# 19_RK3588_1_8V__3_3V_GPIO.net
KiCad netlist of a schematic drawn in Altium Designer
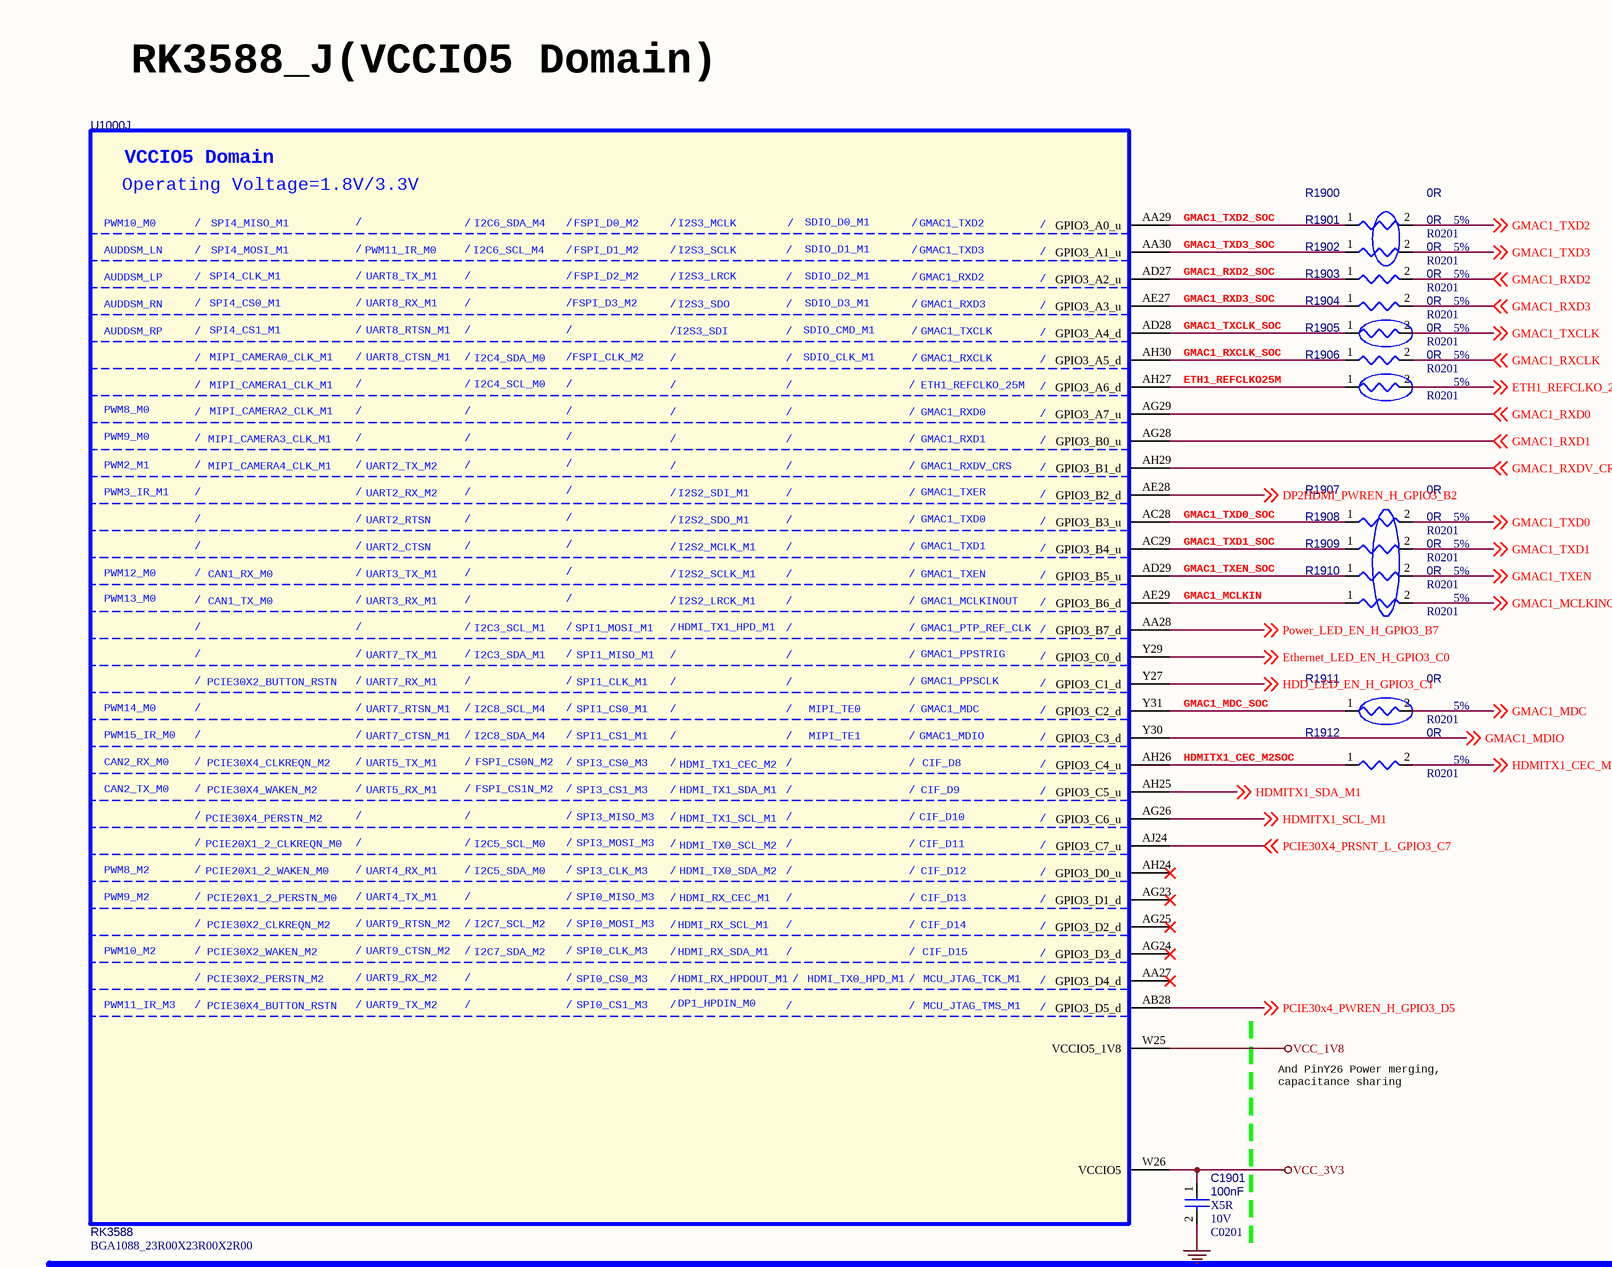
[diagram p0: 19.RK3588_1.8V_ 3.3V GPIO.SchDoc, top left]
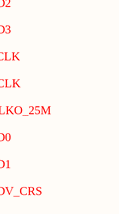
[diagram p1: 19.RK3588_1.8V_ 3.3V GPIO.SchDoc, top right]
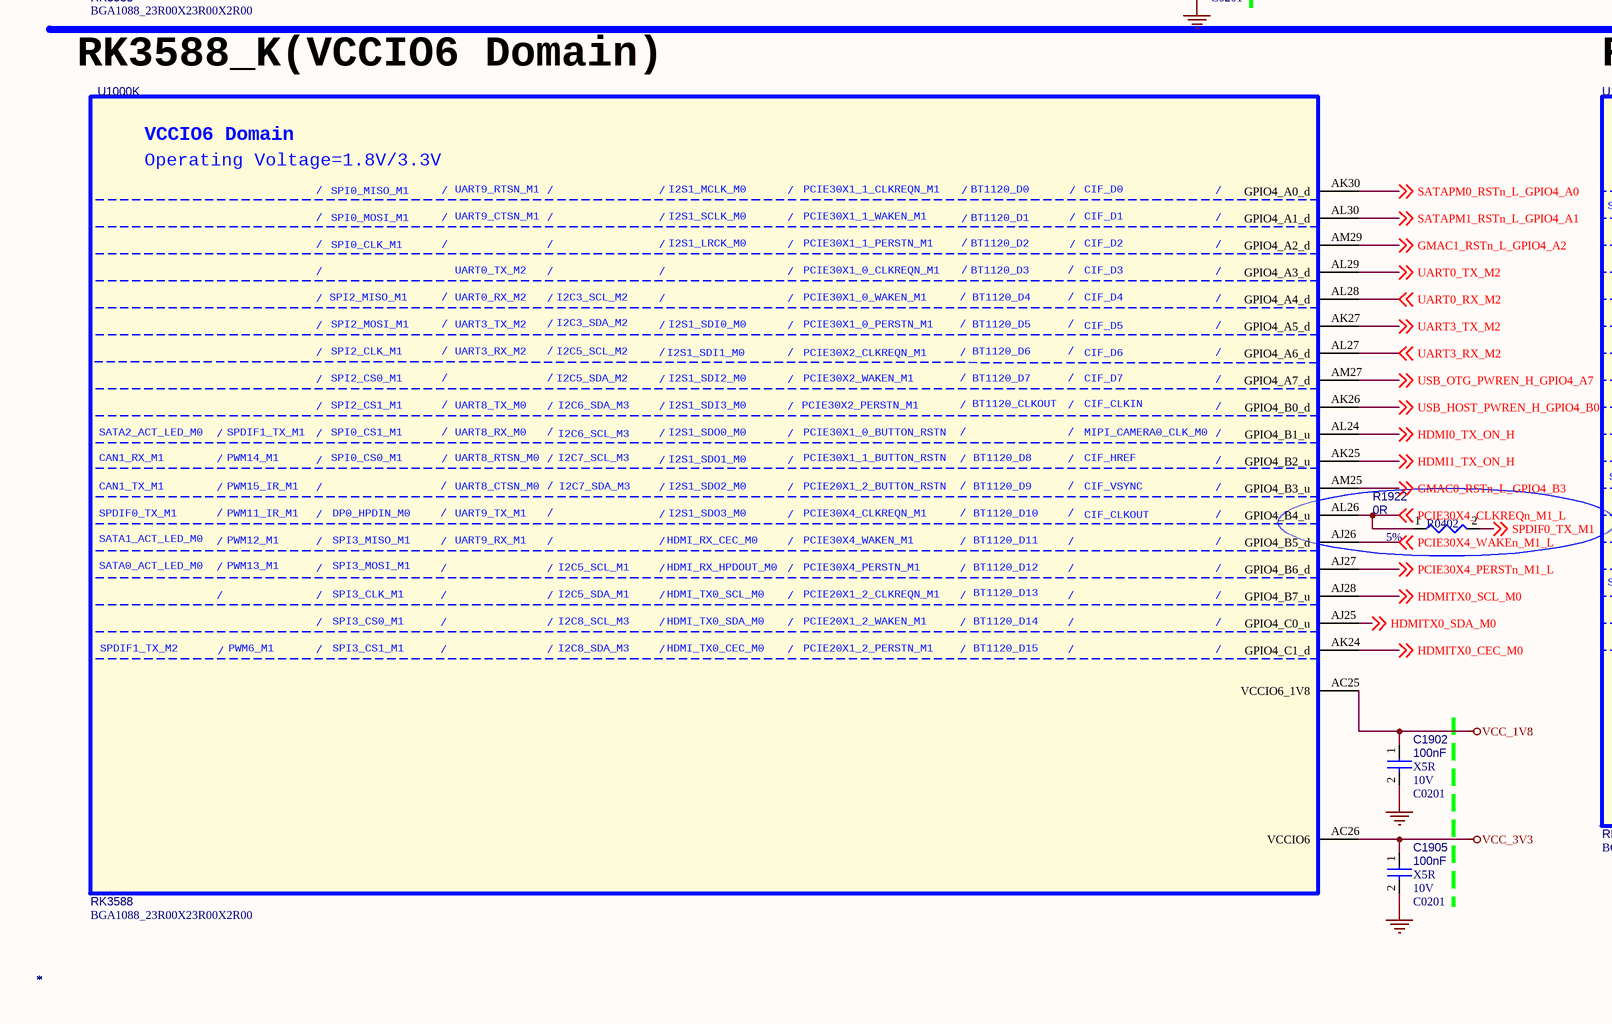
[diagram p2: 19.RK3588_1.8V_ 3.3V GPIO.SchDoc, bottom left]
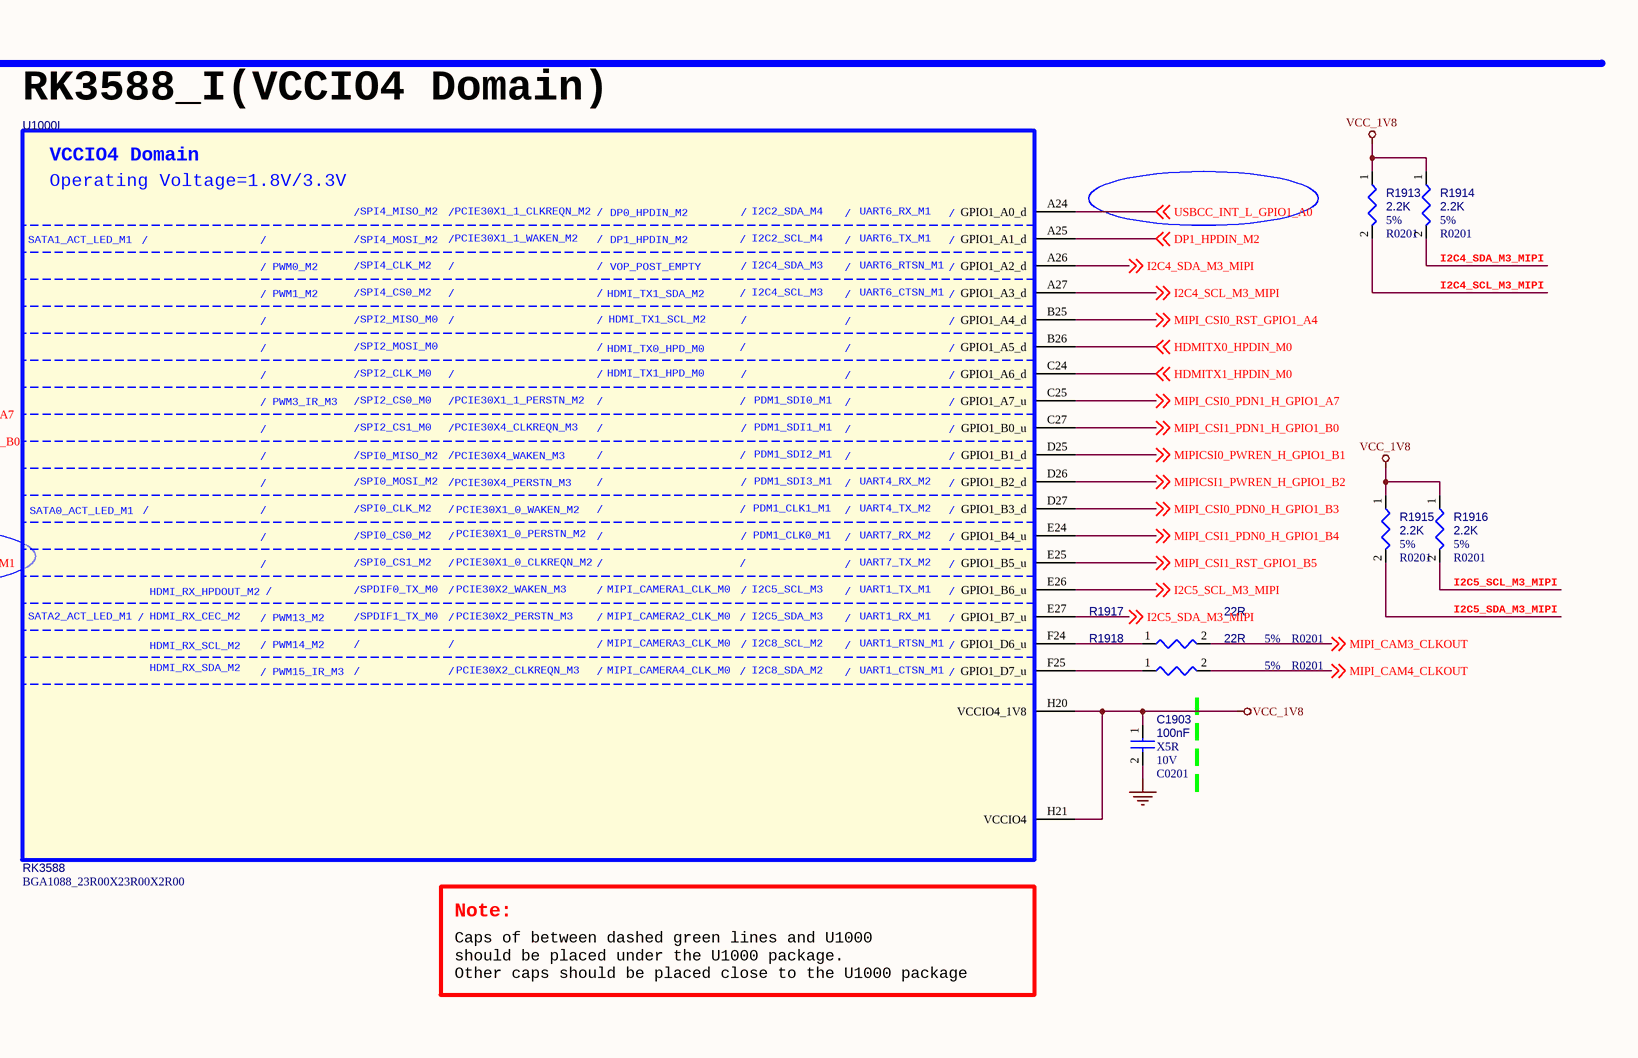
[diagram p3: 19.RK3588_1.8V_ 3.3V GPIO.SchDoc, bottom right]

(export (version "E")
  (design (tool "Eeschema 10.0.6"))
  (components
    (comp (ref "C1901")
      (value "*")
      (footprint "C0201")
      (description "cap,100.00nF,+/-10%,10V,X5R,C0201")
      (fields
        (field (name "VOLTAGE") "10V")
        (field (name "PCB FOOTPRINT") "C0201")
        (field (name "DIELECTRIC") "X5R")
        (field (name "TOLERANCE") "10%")
        (field (name "MANUFACTURER") "TDK")
        (field (name "ALTIUM_UNNAMED_1") "100nF")
        (field (name "CREATED BY") "JJJ")
      )
      (libsource (lib "*") (part "CAP NP"))
    )
    (comp (ref "C1902")
      (value "*")
      (footprint "C0201")
      (description "cap,100.00nF,+/-10%,10V,X5R,C0201")
      (fields
        (field (name "VOLTAGE") "10V")
        (field (name "PCB FOOTPRINT") "C0201")
        (field (name "DIELECTRIC") "X5R")
        (field (name "MANUFACTURER") "TDK")
        (field (name "TOLERANCE") "10%")
        (field (name "ALTIUM_UNNAMED_1") "100nF")
        (field (name "CREATED BY") "JJJ")
      )
      (libsource (lib "*") (part "CAP NP"))
    )
    (comp (ref "C1903")
      (value "*")
      (footprint "C0201")
      (description "cap,100.00nF,+/-10%,10V,X5R,C0201")
      (fields
        (field (name "VOLTAGE") "10V")
        (field (name "PCB FOOTPRINT") "C0201")
        (field (name "DIELECTRIC") "X5R")
        (field (name "MANUFACTURER") "TDK")
        (field (name "TOLERANCE") "10%")
        (field (name "ALTIUM_UNNAMED_1") "100nF")
        (field (name "CREATED BY") "JJJ")
      )
      (libsource (lib "*") (part "CAP NP"))
    )
    (comp (ref "C1905")
      (value "*")
      (footprint "C0201")
      (description "cap,100.00nF,+/-10%,10V,X5R,C0201")
      (fields
        (field (name "VOLTAGE") "10V")
        (field (name "PCB FOOTPRINT") "C0201")
        (field (name "DIELECTRIC") "X5R")
        (field (name "TOLERANCE") "10%")
        (field (name "MANUFACTURER") "TDK")
        (field (name "ALTIUM_UNNAMED_1") "100nF")
        (field (name "CREATED BY") "JJJ")
      )
      (libsource (lib "*") (part "CAP NP"))
    )
    (comp (ref "R1900")
      (value "*")
      (footprint "R0402")
      (description "НЁУГєсД¤µзЧи,0R,+/-5%,R0201,1/20W.")
      (fields
        (field (name "PCB FOOTPRINT") "R0201")
        (field (name "TOLERANCE") "5%")
        (field (name "MANUFACTURER") "YAGEO")
        (field (name "ALTIUM_UNNAMED_1") "0R")
        (field (name "CREATED BY") "YTL")
      )
      (libsource (lib "*") (part "RESISTOR_Dup1"))
    )
    (comp (ref "R1901")
      (value "*")
      (footprint "R0402")
      (description "НЁУГєсД¤µзЧи,0R,+/-5%,R0201,1/20W.")
      (fields
        (field (name "PCB FOOTPRINT") "R0201")
        (field (name "TOLERANCE") "5%")
        (field (name "MANUFACTURER") "YAGEO")
        (field (name "ALTIUM_UNNAMED_1") "0R")
        (field (name "CREATED BY") "YTL")
      )
      (libsource (lib "*") (part "RESISTOR_Dup1"))
    )
    (comp (ref "R1902")
      (value "*")
      (footprint "R0402")
      (description "НЁУГєсД¤µзЧи,0R,+/-5%,R0201,1/20W.")
      (fields
        (field (name "PCB FOOTPRINT") "R0201")
        (field (name "TOLERANCE") "5%")
        (field (name "MANUFACTURER") "YAGEO")
        (field (name "ALTIUM_UNNAMED_1") "0R")
        (field (name "CREATED BY") "YTL")
      )
      (libsource (lib "*") (part "RESISTOR_Dup1"))
    )
    (comp (ref "R1903")
      (value "*")
      (footprint "R0402")
      (description "НЁУГєсД¤µзЧи,0R,+/-5%,R0201,1/20W.")
      (fields
        (field (name "PCB FOOTPRINT") "R0201")
        (field (name "TOLERANCE") "5%")
        (field (name "MANUFACTURER") "YAGEO")
        (field (name "ALTIUM_UNNAMED_1") "0R")
        (field (name "CREATED BY") "YTL")
      )
      (libsource (lib "*") (part "RESISTOR_Dup1"))
    )
    (comp (ref "R1904")
      (value "*")
      (footprint "R0402")
      (description "НЁУГєсД¤µзЧи,0R,+/-5%,R0201,1/20W.")
      (fields
        (field (name "PCB FOOTPRINT") "R0201")
        (field (name "TOLERANCE") "5%")
        (field (name "MANUFACTURER") "YAGEO")
        (field (name "ALTIUM_UNNAMED_1") "0R")
        (field (name "CREATED BY") "YTL")
      )
      (libsource (lib "*") (part "RESISTOR_Dup1"))
    )
    (comp (ref "R1905")
      (value "*")
      (footprint "R0402")
      (description "НЁУГєсД¤µзЧи,0R,+/-5%,R0201,1/20W.")
      (fields
        (field (name "PCB FOOTPRINT") "R0201")
        (field (name "TOLERANCE") "5%")
        (field (name "MANUFACTURER") "YAGEO")
        (field (name "ALTIUM_UNNAMED_1") "0R")
        (field (name "CREATED BY") "YTL")
      )
      (libsource (lib "*") (part "RESISTOR_Dup1"))
    )
    (comp (ref "R1906")
      (value "*")
      (footprint "R0402")
      (description "НЁУГєсД¤µзЧи,0R,+/-5%,R0201,1/20W.")
      (fields
        (field (name "PCB FOOTPRINT") "R0201")
        (field (name "TOLERANCE") "5%")
        (field (name "MANUFACTURER") "YAGEO")
        (field (name "ALTIUM_UNNAMED_1") "0R")
        (field (name "CREATED BY") "YTL")
      )
      (libsource (lib "*") (part "RESISTOR_Dup1"))
    )
    (comp (ref "R1907")
      (value "*")
      (footprint "R0402")
      (description "НЁУГєсД¤µзЧи,0R,+/-5%,R0201,1/20W.")
      (fields
        (field (name "PCB FOOTPRINT") "R0201")
        (field (name "TOLERANCE") "5%")
        (field (name "MANUFACTURER") "YAGEO")
        (field (name "ALTIUM_UNNAMED_1") "0R")
        (field (name "CREATED BY") "YTL")
      )
      (libsource (lib "*") (part "RESISTOR_Dup1"))
    )
    (comp (ref "R1908")
      (value "*")
      (footprint "R0402")
      (description "НЁУГєсД¤µзЧи,0R,+/-5%,R0201,1/20W.")
      (fields
        (field (name "PCB FOOTPRINT") "R0201")
        (field (name "TOLERANCE") "5%")
        (field (name "MANUFACTURER") "YAGEO")
        (field (name "ALTIUM_UNNAMED_1") "0R")
        (field (name "CREATED BY") "YTL")
      )
      (libsource (lib "*") (part "RESISTOR_Dup1"))
    )
    (comp (ref "R1909")
      (value "*")
      (footprint "R0402")
      (description "НЁУГєсД¤µзЧи,0R,+/-5%,R0201,1/20W.")
      (fields
        (field (name "PCB FOOTPRINT") "R0201")
        (field (name "TOLERANCE") "5%")
        (field (name "MANUFACTURER") "YAGEO")
        (field (name "ALTIUM_UNNAMED_1") "0R")
        (field (name "CREATED BY") "YTL")
      )
      (libsource (lib "*") (part "RESISTOR_Dup1"))
    )
    (comp (ref "R1910")
      (value "*")
      (footprint "R0402")
      (description "НЁУГєсД¤µзЧи,0R,+/-5%,R0201,1/20W.")
      (fields
        (field (name "PCB FOOTPRINT") "R0201")
        (field (name "TOLERANCE") "5%")
        (field (name "MANUFACTURER") "YAGEO")
        (field (name "ALTIUM_UNNAMED_1") "0R")
        (field (name "CREATED BY") "YTL")
      )
      (libsource (lib "*") (part "RESISTOR_Dup1"))
    )
    (comp (ref "R1911")
      (value "*")
      (footprint "R0402")
      (description "НЁУГєсД¤µзЧи,0R,+/-5%,R0201,1/20W.")
      (fields
        (field (name "PCB FOOTPRINT") "R0201")
        (field (name "TOLERANCE") "5%")
        (field (name "MANUFACTURER") "YAGEO")
        (field (name "ALTIUM_UNNAMED_1") "0R")
        (field (name "CREATED BY") "YTL")
      )
      (libsource (lib "*") (part "RESISTOR_Dup1"))
    )
    (comp (ref "R1912")
      (value "*")
      (footprint "R0402")
      (description "НЁУГєсД¤µзЧи,0R,+/-5%,R0201,1/20W.")
      (fields
        (field (name "PCB FOOTPRINT") "R0201")
        (field (name "TOLERANCE") "5%")
        (field (name "MANUFACTURER") "YAGEO")
        (field (name "ALTIUM_UNNAMED_1") "0R")
        (field (name "CREATED BY") "YTL")
      )
      (libsource (lib "*") (part "RESISTOR_Dup1"))
    )
    (comp (ref "R1913")
      (value "*")
      (footprint "R0402")
      (description "НЁУГєсД¤µзЧи,2K2,+/-5%,R0201,1/20W.")
      (fields
        (field (name "PCB FOOTPRINT") "R0201")
        (field (name "TOLERANCE") "5%")
        (field (name "MANUFACTURER") "YAGEO")
        (field (name "ALTIUM_UNNAMED_1") "2.2K")
        (field (name "CREATED BY") "YTL")
      )
      (libsource (lib "*") (part "RESISTOR_Dup1"))
    )
    (comp (ref "R1914")
      (value "*")
      (footprint "R0402")
      (description "НЁУГєсД¤µзЧи,2K2,+/-5%,R0201,1/20W.")
      (fields
        (field (name "PCB FOOTPRINT") "R0201")
        (field (name "TOLERANCE") "5%")
        (field (name "MANUFACTURER") "YAGEO")
        (field (name "ALTIUM_UNNAMED_1") "2.2K")
        (field (name "CREATED BY") "YTL")
      )
      (libsource (lib "*") (part "RESISTOR_Dup1"))
    )
    (comp (ref "R1915")
      (value "*")
      (footprint "R0402")
      (description "НЁУГєсД¤µзЧи,2K2,+/-5%,R0201,1/20W.")
      (fields
        (field (name "PCB FOOTPRINT") "R0201")
        (field (name "TOLERANCE") "5%")
        (field (name "MANUFACTURER") "YAGEO")
        (field (name "ALTIUM_UNNAMED_1") "2.2K")
        (field (name "CREATED BY") "YTL")
      )
      (libsource (lib "*") (part "RESISTOR_Dup1"))
    )
    (comp (ref "R1916")
      (value "*")
      (footprint "R0402")
      (description "НЁУГєсД¤µзЧи,2K2,+/-5%,R0201,1/20W.")
      (fields
        (field (name "PCB FOOTPRINT") "R0201")
        (field (name "TOLERANCE") "5%")
        (field (name "MANUFACTURER") "YAGEO")
        (field (name "ALTIUM_UNNAMED_1") "2.2K")
        (field (name "CREATED BY") "YTL")
      )
      (libsource (lib "*") (part "RESISTOR_Dup1"))
    )
    (comp (ref "R1917")
      (value "*")
      (footprint "R0402")
      (description "НЁУГєсД¤µзЧи,22R,+/-5%,R0201,1/20W.")
      (fields
        (field (name "PCB FOOTPRINT") "R0201")
        (field (name "TOLERANCE") "5%")
        (field (name "MANUFACTURER") "YAGEO")
        (field (name "ALTIUM_UNNAMED_1") "22R")
        (field (name "CREATED BY") "YTL")
      )
      (libsource (lib "*") (part "RESISTOR_Dup1"))
    )
    (comp (ref "R1918")
      (value "*")
      (footprint "R0402")
      (description "НЁУГєсД¤µзЧи,22R,+/-5%,R0201,1/20W.")
      (fields
        (field (name "PCB FOOTPRINT") "R0201")
        (field (name "TOLERANCE") "5%")
        (field (name "MANUFACTURER") "YAGEO")
        (field (name "ALTIUM_UNNAMED_1") "22R")
        (field (name "CREATED BY") "YTL")
      )
      (libsource (lib "*") (part "RESISTOR_Dup1"))
    )
    (comp (ref "R1922")
      (value "*")
      (footprint "R0402")
      (description "НЁУГєсД¤µзЧи,0R,+/-5%,R0402,1/16W.")
      (fields
        (field (name "PCB FOOTPRINT") "R0402")
        (field (name "TOLERANCE") "5%")
        (field (name "MANUFACTURER") "YAGEO")
        (field (name "ALTIUM_UNNAMED_1") "0R")
        (field (name "CREATED BY") "YTL")
      )
      (libsource (lib "*") (part "RESISTOR_Dup1"))
    )
    (comp (ref "U1000")
      (value "*")
      (footprint "BGA1088_23R00X23R00X2R00")
      (description "ROCKCHIP SOC")
      (fields
        (field (name "MANUFACTURER") "Rockchip (ИрРѕОў)")
        (field (name "PCB FOOTPRINT") "BGA1088_23R00X23R00X2R00")
        (field (name "ALTIUM_UNNAMED_1") "RK3588")
        (field (name "CREATED BY") "YWQ")
      )
      (libsource (lib "*") (part "SOC_RK3588"))
    )
  )
  (nets
    (net (code "1") (name "/ETH1_REFCLKO25M") (class "Default")
      (node (ref "R1906") (pin "1") (pinfunction "1_1") (pintype "passive"))
      (node (ref "U1000") (pin "AH27") (pinfunction "GPIO3_A6_d_AH27") (pintype "passive"))
    )
    (net (code "2") (name "/GMAC1_MCLKIN") (class "Default")
      (node (ref "R1910") (pin "1") (pinfunction "1_1") (pintype "passive"))
      (node (ref "U1000") (pin "AE29") (pinfunction "GPIO3_B6_d_AE29") (pintype "passive"))
    )
    (net (code "3") (name "/GMAC1_MDC_SOC") (class "Default")
      (node (ref "R1911") (pin "1") (pinfunction "1_1") (pintype "passive"))
      (node (ref "U1000") (pin "Y31") (pinfunction "GPIO3_C2_d_Y31") (pintype "passive"))
    )
    (net (code "4") (name "/GMAC1_RXCLK_SOC") (class "Default")
      (node (ref "R1905") (pin "1") (pinfunction "1_1") (pintype "passive"))
      (node (ref "U1000") (pin "AH30") (pinfunction "GPIO3_A5_d_AH30") (pintype "passive"))
    )
    (net (code "5") (name "/GMAC1_RXD2_SOC") (class "Default")
      (node (ref "R1902") (pin "1") (pinfunction "1_1") (pintype "passive"))
      (node (ref "U1000") (pin "AD27") (pinfunction "GPIO3_A2_u_AD27") (pintype "passive"))
    )
    (net (code "6") (name "/GMAC1_RXD3_SOC") (class "Default")
      (node (ref "R1903") (pin "1") (pinfunction "1_1") (pintype "passive"))
      (node (ref "U1000") (pin "AE27") (pinfunction "GPIO3_A3_u_AE27") (pintype "passive"))
    )
    (net (code "7") (name "/GMAC1_TXCLK_SOC") (class "Default")
      (node (ref "R1904") (pin "1") (pinfunction "1_1") (pintype "passive"))
      (node (ref "U1000") (pin "AD28") (pinfunction "GPIO3_A4_d_AD28") (pintype "passive"))
    )
    (net (code "8") (name "/GMAC1_TXD0_SOC") (class "Default")
      (node (ref "R1907") (pin "1") (pinfunction "1_1") (pintype "passive"))
      (node (ref "U1000") (pin "AC28") (pinfunction "GPIO3_B3_u_AC28") (pintype "passive"))
    )
    (net (code "9") (name "/GMAC1_TXD1_SOC") (class "Default")
      (node (ref "R1908") (pin "1") (pinfunction "1_1") (pintype "passive"))
      (node (ref "U1000") (pin "AC29") (pinfunction "GPIO3_B4_u_AC29") (pintype "passive"))
    )
    (net (code "10") (name "/GMAC1_TXD2_SOC") (class "Default")
      (node (ref "R1900") (pin "1") (pinfunction "1_1") (pintype "passive"))
      (node (ref "U1000") (pin "AA29") (pinfunction "GPIO3_A0_u_AA29") (pintype "passive"))
    )
    (net (code "11") (name "/GMAC1_TXD3_SOC") (class "Default")
      (node (ref "R1901") (pin "1") (pinfunction "1_1") (pintype "passive"))
      (node (ref "U1000") (pin "AA30") (pinfunction "GPIO3_A1_u_AA30") (pintype "passive"))
    )
    (net (code "12") (name "/GMAC1_TXEN_SOC") (class "Default")
      (node (ref "R1909") (pin "1") (pinfunction "1_1") (pintype "passive"))
      (node (ref "U1000") (pin "AD29") (pinfunction "GPIO3_B5_u_AD29") (pintype "passive"))
    )
    (net (code "13") (name "/HDMITX1_CEC_M2SOC") (class "Default")
      (node (ref "R1912") (pin "1") (pinfunction "1_1") (pintype "passive"))
      (node (ref "U1000") (pin "AH26") (pinfunction "GPIO3_C4_u_AH26") (pintype "passive"))
    )
    (net (code "14") (name "DP1_HPDIN_M2") (class "Default")
      (node (ref "U1000") (pin "A25") (pinfunction "GPIO1_A1_d_A25") (pintype "passive"))
    )
    (net (code "15") (name "DP2HDMI_PWREN_H_GPIO3_B2") (class "Default")
      (node (ref "U1000") (pin "AE28") (pinfunction "GPIO3_B2_d_AE28") (pintype "passive"))
    )
    (net (code "16") (name "ETH1_REFCLKO_25M") (class "Default")
      (node (ref "R1906") (pin "2") (pinfunction "2_2") (pintype "passive"))
    )
    (net (code "17") (name "Ethernet_LED_EN_H_GPIO3_C0") (class "Default")
      (node (ref "U1000") (pin "Y29") (pinfunction "GPIO3_C0_d_Y29") (pintype "passive"))
    )
    (net (code "18") (name "GMAC0_RSTn_L_GPIO4_B3") (class "Default")
      (node (ref "U1000") (pin "AM25") (pinfunction "GPIO4_B3_u_AM25") (pintype "passive"))
    )
    (net (code "19") (name "GMAC1_MCLKINOUT") (class "Default")
      (node (ref "R1910") (pin "2") (pinfunction "2_2") (pintype "passive"))
    )
    (net (code "20") (name "GMAC1_MDC") (class "Default")
      (node (ref "R1911") (pin "2") (pinfunction "2_2") (pintype "passive"))
    )
    (net (code "21") (name "GMAC1_MDIO") (class "Default")
      (node (ref "U1000") (pin "Y30") (pinfunction "GPIO3_C3_d_Y30") (pintype "passive"))
    )
    (net (code "22") (name "GMAC1_RSTn_L_GPIO4_A2") (class "Default")
      (node (ref "U1000") (pin "AM29") (pinfunction "GPIO4_A2_d_AM29") (pintype "passive"))
    )
    (net (code "23") (name "GMAC1_RXCLK") (class "Default")
      (node (ref "R1905") (pin "2") (pinfunction "2_2") (pintype "passive"))
    )
    (net (code "24") (name "GMAC1_RXD0") (class "Default")
      (node (ref "U1000") (pin "AG29") (pinfunction "GPIO3_A7_u_AG29") (pintype "passive"))
    )
    (net (code "25") (name "GMAC1_RXD1") (class "Default")
      (node (ref "U1000") (pin "AG28") (pinfunction "GPIO3_B0_u_AG28") (pintype "passive"))
    )
    (net (code "26") (name "GMAC1_RXD2") (class "Default")
      (node (ref "R1902") (pin "2") (pinfunction "2_2") (pintype "passive"))
    )
    (net (code "27") (name "GMAC1_RXD3") (class "Default")
      (node (ref "R1903") (pin "2") (pinfunction "2_2") (pintype "passive"))
    )
    (net (code "28") (name "GMAC1_RXDV_CRS") (class "Default")
      (node (ref "U1000") (pin "AH29") (pinfunction "GPIO3_B1_d_AH29") (pintype "passive"))
    )
    (net (code "29") (name "GMAC1_TXCLK") (class "Default")
      (node (ref "R1904") (pin "2") (pinfunction "2_2") (pintype "passive"))
    )
    (net (code "30") (name "GMAC1_TXD0") (class "Default")
      (node (ref "R1907") (pin "2") (pinfunction "2_2") (pintype "passive"))
    )
    (net (code "31") (name "GMAC1_TXD1") (class "Default")
      (node (ref "R1908") (pin "2") (pinfunction "2_2") (pintype "passive"))
    )
    (net (code "32") (name "GMAC1_TXD2") (class "Default")
      (node (ref "R1900") (pin "2") (pinfunction "2_2") (pintype "passive"))
    )
    (net (code "33") (name "GMAC1_TXD3") (class "Default")
      (node (ref "R1901") (pin "2") (pinfunction "2_2") (pintype "passive"))
    )
    (net (code "34") (name "GMAC1_TXEN") (class "Default")
      (node (ref "R1909") (pin "2") (pinfunction "2_2") (pintype "passive"))
    )
    (net (code "35") (name "GND") (class "Default")
      (node (ref "C1901") (pin "2") (pinfunction "2_2") (pintype "passive"))
      (node (ref "C1902") (pin "2") (pinfunction "2_2") (pintype "passive"))
      (node (ref "C1903") (pin "2") (pinfunction "2_2") (pintype "passive"))
      (node (ref "C1905") (pin "2") (pinfunction "2_2") (pintype "passive"))
    )
    (net (code "36") (name "HDD_LED_EN_H_GPIO3_C1") (class "Default")
      (node (ref "U1000") (pin "Y27") (pinfunction "GPIO3_C1_d_Y27") (pintype "passive"))
    )
    (net (code "37") (name "HDMI0_TX_ON_H") (class "Default")
      (node (ref "U1000") (pin "AL24") (pinfunction "GPIO4_B1_u_AL24") (pintype "passive"))
    )
    (net (code "38") (name "HDMI1_TX_ON_H") (class "Default")
      (node (ref "U1000") (pin "AK25") (pinfunction "GPIO4_B2_u_AK25") (pintype "passive"))
    )
    (net (code "39") (name "HDMITX0_CEC_M0") (class "Default")
      (node (ref "U1000") (pin "AK24") (pinfunction "GPIO4_C1_d_AK24") (pintype "passive"))
    )
    (net (code "40") (name "HDMITX0_HPDIN_M0") (class "Default")
      (node (ref "U1000") (pin "B26") (pinfunction "GPIO1_A5_d_B26") (pintype "passive"))
    )
    (net (code "41") (name "HDMITX0_SCL_M0") (class "Default")
      (node (ref "U1000") (pin "AJ28") (pinfunction "GPIO4_B7_u_AJ28") (pintype "passive"))
    )
    (net (code "42") (name "HDMITX0_SDA_M0") (class "Default")
      (node (ref "U1000") (pin "AJ25") (pinfunction "GPIO4_C0_u_AJ25") (pintype "passive"))
    )
    (net (code "43") (name "HDMITX1_CEC_M2") (class "Default")
      (node (ref "R1912") (pin "2") (pinfunction "2_2") (pintype "passive"))
    )
    (net (code "44") (name "HDMITX1_HPDIN_M0") (class "Default")
      (node (ref "U1000") (pin "C24") (pinfunction "GPIO1_A6_d_C24") (pintype "passive"))
    )
    (net (code "45") (name "HDMITX1_SCL_M1") (class "Default")
      (node (ref "U1000") (pin "AG26") (pinfunction "GPIO3_C6_u_AG26") (pintype "passive"))
    )
    (net (code "46") (name "HDMITX1_SDA_M1") (class "Default")
      (node (ref "U1000") (pin "AH25") (pinfunction "GPIO3_C5_u_AH25") (pintype "passive"))
    )
    (net (code "47") (name "I2C4_SCL_M3_MIPI") (class "Default")
      (node (ref "R1913") (pin "2") (pinfunction "2_2") (pintype "passive"))
      (node (ref "U1000") (pin "A27") (pinfunction "GPIO1_A3_d_A27") (pintype "passive"))
    )
    (net (code "48") (name "I2C4_SDA_M3_MIPI") (class "Default")
      (node (ref "R1914") (pin "2") (pinfunction "2_2") (pintype "passive"))
      (node (ref "U1000") (pin "A26") (pinfunction "GPIO1_A2_d_A26") (pintype "passive"))
    )
    (net (code "49") (name "I2C5_SCL_M3_MIPI") (class "Default")
      (node (ref "R1916") (pin "2") (pinfunction "2_2") (pintype "passive"))
      (node (ref "U1000") (pin "E26") (pinfunction "GPIO1_B6_u_E26") (pintype "passive"))
    )
    (net (code "50") (name "I2C5_SDA_M3_MIPI") (class "Default")
      (node (ref "R1915") (pin "2") (pinfunction "2_2") (pintype "passive"))
      (node (ref "U1000") (pin "E27") (pinfunction "GPIO1_B7_u_E27") (pintype "passive"))
    )
    (net (code "51") (name "MIPICSI0_PWREN_H_GPIO1_B1") (class "Default")
      (node (ref "U1000") (pin "D25") (pinfunction "GPIO1_B1_d_D25") (pintype "passive"))
    )
    (net (code "52") (name "MIPICSI1_PWREN_H_GPIO1_B2") (class "Default")
      (node (ref "U1000") (pin "D26") (pinfunction "GPIO1_B2_d_D26") (pintype "passive"))
    )
    (net (code "53") (name "MIPI_CAM3_CLKOUT") (class "Default")
      (node (ref "R1917") (pin "2") (pinfunction "2_2") (pintype "passive"))
    )
    (net (code "54") (name "MIPI_CAM4_CLKOUT") (class "Default")
      (node (ref "R1918") (pin "2") (pinfunction "2_2") (pintype "passive"))
    )
    (net (code "55") (name "MIPI_CSI0_PDN0_H_GPIO1_B3") (class "Default")
      (node (ref "U1000") (pin "D27") (pinfunction "GPIO1_B3_d_D27") (pintype "passive"))
    )
    (net (code "56") (name "MIPI_CSI0_PDN1_H_GPIO1_A7") (class "Default")
      (node (ref "U1000") (pin "C25") (pinfunction "GPIO1_A7_u_C25") (pintype "passive"))
    )
    (net (code "57") (name "MIPI_CSI0_RST_GPIO1_A4") (class "Default")
      (node (ref "U1000") (pin "B25") (pinfunction "GPIO1_A4_d_B25") (pintype "passive"))
    )
    (net (code "58") (name "MIPI_CSI1_PDN0_H_GPIO1_B4") (class "Default")
      (node (ref "U1000") (pin "E24") (pinfunction "GPIO1_B4_u_E24") (pintype "passive"))
    )
    (net (code "59") (name "MIPI_CSI1_PDN1_H_GPIO1_B0") (class "Default")
      (node (ref "U1000") (pin "C27") (pinfunction "GPIO1_B0_u_C27") (pintype "passive"))
    )
    (net (code "60") (name "MIPI_CSI1_RST_GPIO1_B5") (class "Default")
      (node (ref "U1000") (pin "E25") (pinfunction "GPIO1_B5_u_E25") (pintype "passive"))
    )
    (net (code "61") (name "Net-(U1000I-GPIO1_D6_u)") (class "Default")
      (node (ref "R1917") (pin "1") (pinfunction "1_1") (pintype "passive"))
      (node (ref "U1000") (pin "F24") (pinfunction "GPIO1_D6_u_F24") (pintype "passive"))
    )
    (net (code "62") (name "Net-(U1000I-GPIO1_D7_u)") (class "Default")
      (node (ref "R1918") (pin "1") (pinfunction "1_1") (pintype "passive"))
      (node (ref "U1000") (pin "F25") (pinfunction "GPIO1_D7_u_F25") (pintype "passive"))
    )
    (net (code "63") (name "PCIE30X4_CLKREQn_M1_L") (class "Default")
      (node (ref "R1922") (pin "1") (pinfunction "1_1") (pintype "passive"))
      (node (ref "U1000") (pin "AL26") (pinfunction "GPIO4_B4_u_AL26") (pintype "passive"))
    )
    (net (code "64") (name "PCIE30X4_PERSTn_M1_L") (class "Default")
      (node (ref "U1000") (pin "AJ27") (pinfunction "GPIO4_B6_d_AJ27") (pintype "passive"))
    )
    (net (code "65") (name "PCIE30X4_PRSNT_L_GPIO3_C7") (class "Default")
      (node (ref "U1000") (pin "AJ24") (pinfunction "GPIO3_C7_u_AJ24") (pintype "passive"))
    )
    (net (code "66") (name "PCIE30X4_WAKEn_M1_L") (class "Default")
      (node (ref "U1000") (pin "AJ26") (pinfunction "GPIO4_B5_d_AJ26") (pintype "passive"))
    )
    (net (code "67") (name "PCIE30x4_PWREN_H_GPIO3_D5") (class "Default")
      (node (ref "U1000") (pin "AB28") (pinfunction "GPIO3_D5_d_AB28") (pintype "passive"))
    )
    (net (code "68") (name "Power_LED_EN_H_GPIO3_B7") (class "Default")
      (node (ref "U1000") (pin "AA28") (pinfunction "GPIO3_B7_d_AA28") (pintype "passive"))
    )
    (net (code "69") (name "SATAPM0_RSTn_L_GPIO4_A0") (class "Default")
      (node (ref "U1000") (pin "AK30") (pinfunction "GPIO4_A0_d_AK30") (pintype "passive"))
    )
    (net (code "70") (name "SATAPM1_RSTn_L_GPIO4_A1") (class "Default")
      (node (ref "U1000") (pin "AL30") (pinfunction "GPIO4_A1_d_AL30") (pintype "passive"))
    )
    (net (code "71") (name "SPDIF0_TX_M1") (class "Default")
      (node (ref "R1922") (pin "2") (pinfunction "2_2") (pintype "passive"))
    )
    (net (code "72") (name "UART0_RX_M2") (class "Default")
      (node (ref "U1000") (pin "AL28") (pinfunction "GPIO4_A4_d_AL28") (pintype "passive"))
    )
    (net (code "73") (name "UART0_TX_M2") (class "Default")
      (node (ref "U1000") (pin "AL29") (pinfunction "GPIO4_A3_d_AL29") (pintype "passive"))
    )
    (net (code "74") (name "UART3_RX_M2") (class "Default")
      (node (ref "U1000") (pin "AL27") (pinfunction "GPIO4_A6_d_AL27") (pintype "passive"))
    )
    (net (code "75") (name "UART3_TX_M2") (class "Default")
      (node (ref "U1000") (pin "AK27") (pinfunction "GPIO4_A5_d_AK27") (pintype "passive"))
    )
    (net (code "76") (name "USBCC_INT_L_GPIO1_A0") (class "Default")
      (node (ref "U1000") (pin "A24") (pinfunction "GPIO1_A0_d_A24") (pintype "passive"))
    )
    (net (code "77") (name "USB_HOST_PWREN_H_GPIO4_B0") (class "Default")
      (node (ref "U1000") (pin "AK26") (pinfunction "GPIO4_B0_d_AK26") (pintype "passive"))
    )
    (net (code "78") (name "USB_OTG_PWREN_H_GPIO4_A7") (class "Default")
      (node (ref "U1000") (pin "AM27") (pinfunction "GPIO4_A7_d_AM27") (pintype "passive"))
    )
    (net (code "79") (name "VCC_1V8") (class "Default")
      (node (ref "C1902") (pin "1") (pinfunction "1_1") (pintype "passive"))
      (node (ref "C1903") (pin "1") (pinfunction "1_1") (pintype "passive"))
      (node (ref "R1913") (pin "1") (pinfunction "1_1") (pintype "passive"))
      (node (ref "R1914") (pin "1") (pinfunction "1_1") (pintype "passive"))
      (node (ref "R1915") (pin "1") (pinfunction "1_1") (pintype "passive"))
      (node (ref "R1916") (pin "1") (pinfunction "1_1") (pintype "passive"))
      (node (ref "U1000") (pin "AC25") (pinfunction "VCCIO6_1V8_AC25") (pintype "passive"))
      (node (ref "U1000") (pin "H20") (pinfunction "VCCIO4_1V8_H20") (pintype "passive"))
      (node (ref "U1000") (pin "H21") (pinfunction "VCCIO4_H21") (pintype "passive"))
      (node (ref "U1000") (pin "W25") (pinfunction "VCCIO5_1V8_W25") (pintype "passive"))
    )
    (net (code "80") (name "VCC_3V3") (class "Default")
      (node (ref "C1901") (pin "1") (pinfunction "1_1") (pintype "passive"))
      (node (ref "C1905") (pin "1") (pinfunction "1_1") (pintype "passive"))
      (node (ref "U1000") (pin "AC26") (pinfunction "VCCIO6_AC26") (pintype "passive"))
      (node (ref "U1000") (pin "W26") (pinfunction "VCCIO5_W26") (pintype "passive"))
    )
    (net (code "81") (name "unconnected-(U1000J-GPIO3_D0_u-PadAH24)") (class "Default")
      (node (ref "U1000") (pin "AH24") (pinfunction "GPIO3_D0_u_AH24") (pintype "passive+no_connect"))
    )
    (net (code "82") (name "unconnected-(U1000J-GPIO3_D1_d-PadAG23)") (class "Default")
      (node (ref "U1000") (pin "AG23") (pinfunction "GPIO3_D1_d_AG23") (pintype "passive+no_connect"))
    )
    (net (code "83") (name "unconnected-(U1000J-GPIO3_D2_d-PadAG25)") (class "Default")
      (node (ref "U1000") (pin "AG25") (pinfunction "GPIO3_D2_d_AG25") (pintype "passive+no_connect"))
    )
    (net (code "84") (name "unconnected-(U1000J-GPIO3_D3_d-PadAG24)") (class "Default")
      (node (ref "U1000") (pin "AG24") (pinfunction "GPIO3_D3_d_AG24") (pintype "passive+no_connect"))
    )
    (net (code "85") (name "unconnected-(U1000J-GPIO3_D4_d-PadAA27)") (class "Default")
      (node (ref "U1000") (pin "AA27") (pinfunction "GPIO3_D4_d_AA27") (pintype "passive+no_connect"))
    )
  )
)
